# BGC_main.net
KiCad netlist of a schematic drawn in EAGLE
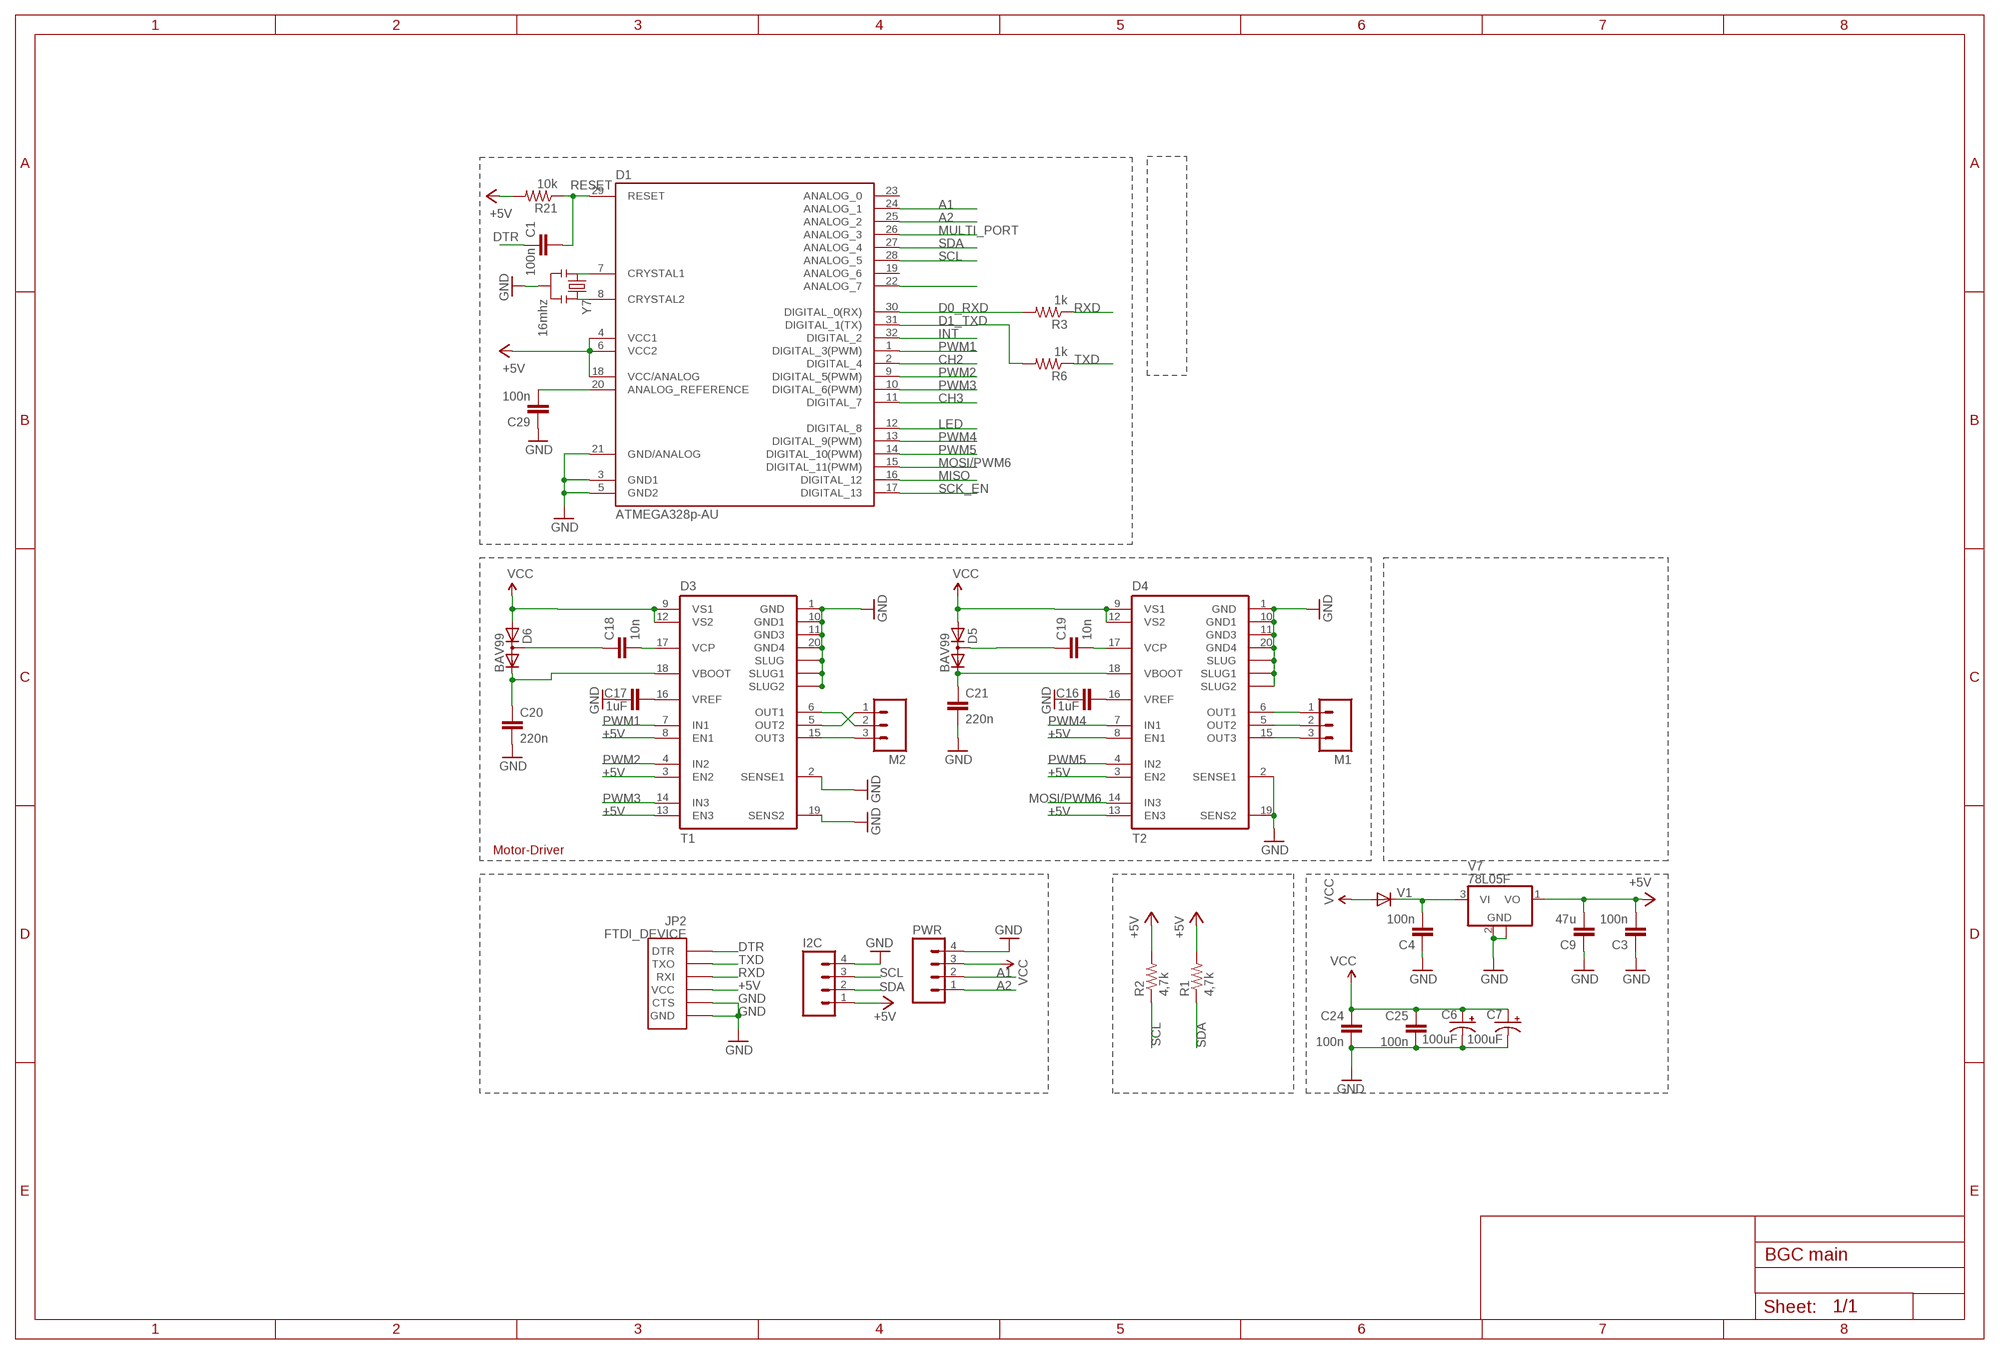
[diagram p0: schematic, sheet 1]

(export (version "E")
  (design (tool "Eeschema 10.0.6"))
  (components
    (comp (ref "C1")
      (value "100n")
      (footprint "eagle-import:0402-CAP")
      (libsource (lib "eagle-import") (part "CAP0402-CAP"))
    )
    (comp (ref "C3")
      (value "100n")
      (footprint "eagle-import:0402-CAP")
      (libsource (lib "eagle-import") (part "CAP0402-CAP"))
    )
    (comp (ref "C4")
      (value "100n")
      (footprint "eagle-import:0402-CAP")
      (libsource (lib "eagle-import") (part "CAP0402-CAP"))
    )
    (comp (ref "C6")
      (value "100uF")
      (footprint "eagle-import:EIA7343")
      (libsource (lib "eagle-import") (part "100UF-10V-10%(TANT)"))
    )
    (comp (ref "C7")
      (value "100uF")
      (footprint "eagle-import:EIA7343")
      (libsource (lib "eagle-import") (part "100UF-10V-10%(TANT)"))
    )
    (comp (ref "C9")
      (value "47u")
      (footprint "eagle-import:C1210")
      (libsource (lib "eagle-import") (part "C-EUC1210"))
    )
    (comp (ref "C16")
      (value "1uF")
      (footprint "eagle-import:0402-CAP")
      (libsource (lib "eagle-import") (part "CAP0402-CAP"))
    )
    (comp (ref "C17")
      (value "1uF")
      (footprint "eagle-import:0402-CAP")
      (libsource (lib "eagle-import") (part "CAP0402-CAP"))
    )
    (comp (ref "C18")
      (value "10n")
      (footprint "eagle-import:0402-CAP")
      (libsource (lib "eagle-import") (part "CAP0402-CAP"))
    )
    (comp (ref "C19")
      (value "10n")
      (footprint "eagle-import:0402-CAP")
      (libsource (lib "eagle-import") (part "CAP0402-CAP"))
    )
    (comp (ref "C20")
      (value "220n")
      (footprint "eagle-import:0402-CAP")
      (libsource (lib "eagle-import") (part "CAP0402-CAP"))
    )
    (comp (ref "C21")
      (value "220n")
      (footprint "eagle-import:0402-CAP")
      (libsource (lib "eagle-import") (part "CAP0402-CAP"))
    )
    (comp (ref "C24")
      (value "100n")
      (footprint "eagle-import:0402-CAP")
      (libsource (lib "eagle-import") (part "CAP0402-CAP"))
    )
    (comp (ref "C25")
      (value "100n")
      (footprint "eagle-import:0402-CAP")
      (libsource (lib "eagle-import") (part "CAP0402-CAP"))
    )
    (comp (ref "C29")
      (value "100n")
      (footprint "eagle-import:0402-CAP")
      (libsource (lib "eagle-import") (part "CAP0402-CAP"))
    )
    (comp (ref "D1")
      (value "ATMEGA328p-AU")
      (footprint "eagle-import:TQFP32-08")
      (libsource (lib "eagle-import") (part "ATMEGA168-AU"))
    )
    (comp (ref "D3")
      (value "T1")
      (footprint "eagle-import:SO20POWER2")
      (libsource (lib "eagle-import") (part "L6234"))
    )
    (comp (ref "D4")
      (value "T2")
      (footprint "eagle-import:SO20POWER2")
      (libsource (lib "eagle-import") (part "L6234"))
    )
    (comp (ref "D5")
      (value "BAV99")
      (footprint "eagle-import:SOT23")
      (libsource (lib "eagle-import") (part "BAV199"))
    )
    (comp (ref "D6")
      (value "BAV99")
      (footprint "eagle-import:SOT23")
      (libsource (lib "eagle-import") (part "BAV199"))
    )
    (comp (ref "I2C")
      (value "M04PTH")
      (footprint "eagle-import:1X04")
      (libsource (lib "eagle-import") (part "M04PTH"))
    )
    (comp (ref "JP2")
      (value "FTDI_DEVICE")
      (footprint "eagle-import:FTDI_DEVICE_SIDE")
      (libsource (lib "eagle-import") (part "FTDI_DEVICE"))
    )
    (comp (ref "M1")
      (value "M03PTH")
      (footprint "eagle-import:1X03")
      (libsource (lib "eagle-import") (part "M03PTH"))
    )
    (comp (ref "M2")
      (value "M03PTH")
      (footprint "eagle-import:1X03")
      (libsource (lib "eagle-import") (part "M03PTH"))
    )
    (comp (ref "PWR")
      (value "M04PTH")
      (footprint "eagle-import:1X04")
      (libsource (lib "eagle-import") (part "M04PTH"))
    )
    (comp (ref "R1")
      (value "4,7k")
      (footprint "eagle-import:0402-RES")
      (libsource (lib "eagle-import") (part "RESISTOR0402-RES"))
    )
    (comp (ref "R2")
      (value "4,7k")
      (footprint "eagle-import:0402-RES")
      (libsource (lib "eagle-import") (part "RESISTOR0402-RES"))
    )
    (comp (ref "R3")
      (value "1k")
      (footprint "eagle-import:0402-RES")
      (libsource (lib "eagle-import") (part "RESISTOR0402-RES"))
    )
    (comp (ref "R6")
      (value "1k")
      (footprint "eagle-import:0402-RES")
      (libsource (lib "eagle-import") (part "RESISTOR0402-RES"))
    )
    (comp (ref "R21")
      (value "10k")
      (footprint "eagle-import:0402-RES")
      (libsource (lib "eagle-import") (part "RESISTOR0402-RES"))
    )
    (comp (ref "V1")
      (value "DIODE-DO214AC")
      (footprint "eagle-import:DO214AC")
      (libsource (lib "eagle-import") (part "DIODE-DO214AC"))
    )
    (comp (ref "V7")
      (value "78L05F")
      (footprint "eagle-import:SOT89")
      (libsource (lib "eagle-import") (part "78LF05"))
    )
    (comp (ref "Y7")
      (value "16mhz")
      (footprint "eagle-import:RESONATOR-SMD")
      (libsource (lib "eagle-import") (part "RESONATORSMD"))
    )
  )
  (nets
    (net (code "1") (name "+5V") (class "Default")
      (node (ref "C3") (pin "2") (pinfunction "2_2") (pintype "passive"))
      (node (ref "C9") (pin "2") (pinfunction "2_2") (pintype "passive"))
      (node (ref "D1") (pin "18") (pinfunction "VCC/ANALOG_18") (pintype "passive"))
      (node (ref "D1") (pin "4") (pinfunction "VCC1_4") (pintype "power_in"))
      (node (ref "D1") (pin "6") (pinfunction "VCC2_6") (pintype "power_in"))
      (node (ref "D3") (pin "13") (pinfunction "EN3_13") (pintype "output"))
      (node (ref "D3") (pin "3") (pinfunction "EN2_3") (pintype "input"))
      (node (ref "D3") (pin "8") (pinfunction "EN1_8") (pintype "bidirectional"))
      (node (ref "D4") (pin "13") (pinfunction "EN3_13") (pintype "output"))
      (node (ref "D4") (pin "3") (pinfunction "EN2_3") (pintype "input"))
      (node (ref "D4") (pin "8") (pinfunction "EN1_8") (pintype "bidirectional"))
      (node (ref "I2C") (pin "1") (pinfunction "1_1") (pintype "passive"))
      (node (ref "JP2") (pin "P$4") (pinfunction "VCC_P$4") (pintype "bidirectional"))
      (node (ref "R1") (pin "2") (pinfunction "2_2") (pintype "passive"))
      (node (ref "R2") (pin "2") (pinfunction "2_2") (pintype "passive"))
      (node (ref "R21") (pin "2") (pinfunction "2_2") (pintype "passive"))
      (node (ref "V7") (pin "1") (pinfunction "VO_1") (pintype "passive"))
    )
    (net (code "2") (name "/A1") (class "Default")
      (node (ref "D1") (pin "24") (pinfunction "ANALOG_1_24") (pintype "bidirectional"))
      (node (ref "PWR") (pin "2") (pinfunction "2_2") (pintype "passive"))
    )
    (net (code "3") (name "/A2") (class "Default")
      (node (ref "D1") (pin "25") (pinfunction "ANALOG_2_25") (pintype "bidirectional"))
      (node (ref "PWR") (pin "1") (pinfunction "1_1") (pintype "passive"))
    )
    (net (code "4") (name "/CH2") (class "Default")
      (node (ref "D1") (pin "2") (pinfunction "DIGITAL_4_2") (pintype "bidirectional"))
    )
    (net (code "5") (name "/CH3") (class "Default")
      (node (ref "D1") (pin "11") (pinfunction "DIGITAL_7_11") (pintype "bidirectional"))
    )
    (net (code "6") (name "/D0_RXD") (class "Default")
      (node (ref "D1") (pin "30") (pinfunction "DIGITAL_0(RX)_30") (pintype "bidirectional"))
      (node (ref "R3") (pin "2") (pinfunction "2_2") (pintype "passive"))
    )
    (net (code "7") (name "/D1_TXD") (class "Default")
      (node (ref "D1") (pin "31") (pinfunction "DIGITAL_1(TX)_31") (pintype "bidirectional"))
      (node (ref "R6") (pin "2") (pinfunction "2_2") (pintype "passive"))
    )
    (net (code "8") (name "/DTR") (class "Default")
      (node (ref "C1") (pin "1") (pinfunction "1_1") (pintype "passive"))
      (node (ref "JP2") (pin "P$1") (pinfunction "DTR_P$1") (pintype "bidirectional"))
    )
    (net (code "9") (name "/INT") (class "Default")
      (node (ref "D1") (pin "32") (pinfunction "DIGITAL_2_32") (pintype "bidirectional"))
    )
    (net (code "10") (name "/LED") (class "Default")
      (node (ref "D1") (pin "12") (pinfunction "DIGITAL_8_12") (pintype "bidirectional"))
    )
    (net (code "11") (name "/MISO") (class "Default")
      (node (ref "D1") (pin "16") (pinfunction "DIGITAL_12_16") (pintype "bidirectional"))
    )
    (net (code "12") (name "/MOSI{slash}PWM6") (class "Default")
      (node (ref "D1") (pin "15") (pinfunction "DIGITAL_11(PWM)_15") (pintype "bidirectional"))
      (node (ref "D4") (pin "14") (pinfunction "IN3_14") (pintype "bidirectional"))
    )
    (net (code "13") (name "/MULTI_PORT") (class "Default")
      (node (ref "D1") (pin "26") (pinfunction "ANALOG_3_26") (pintype "bidirectional"))
    )
    (net (code "14") (name "/PWM1") (class "Default")
      (node (ref "D1") (pin "1") (pinfunction "DIGITAL_3(PWM)_1") (pintype "bidirectional"))
      (node (ref "D3") (pin "7") (pinfunction "IN1_7") (pintype "input"))
    )
    (net (code "15") (name "/PWM2") (class "Default")
      (node (ref "D1") (pin "9") (pinfunction "DIGITAL_5(PWM)_9") (pintype "bidirectional"))
      (node (ref "D3") (pin "4") (pinfunction "IN2_4") (pintype "input"))
    )
    (net (code "16") (name "/PWM3") (class "Default")
      (node (ref "D1") (pin "10") (pinfunction "DIGITAL_6(PWM)_10") (pintype "bidirectional"))
      (node (ref "D3") (pin "14") (pinfunction "IN3_14") (pintype "bidirectional"))
    )
    (net (code "17") (name "/PWM4") (class "Default")
      (node (ref "D1") (pin "13") (pinfunction "DIGITAL_9(PWM)_13") (pintype "bidirectional"))
      (node (ref "D4") (pin "7") (pinfunction "IN1_7") (pintype "input"))
    )
    (net (code "18") (name "/PWM5") (class "Default")
      (node (ref "D1") (pin "14") (pinfunction "DIGITAL_10(PWM)_14") (pintype "bidirectional"))
      (node (ref "D4") (pin "4") (pinfunction "IN2_4") (pintype "input"))
    )
    (net (code "19") (name "/RESET") (class "Default")
      (node (ref "C1") (pin "2") (pinfunction "2_2") (pintype "passive"))
      (node (ref "D1") (pin "29") (pinfunction "RESET_29") (pintype "bidirectional"))
      (node (ref "R21") (pin "1") (pinfunction "1_1") (pintype "passive"))
    )
    (net (code "20") (name "/RXD") (class "Default")
      (node (ref "JP2") (pin "P$3") (pinfunction "RXI_P$3") (pintype "bidirectional"))
      (node (ref "R3") (pin "1") (pinfunction "1_1") (pintype "passive"))
    )
    (net (code "21") (name "/SCK_EN") (class "Default")
      (node (ref "D1") (pin "17") (pinfunction "DIGITAL_13_17") (pintype "bidirectional"))
    )
    (net (code "22") (name "/SCL") (class "Default")
      (node (ref "D1") (pin "28") (pinfunction "ANALOG_5_28") (pintype "bidirectional"))
      (node (ref "I2C") (pin "3") (pinfunction "3_3") (pintype "passive"))
      (node (ref "R2") (pin "1") (pinfunction "1_1") (pintype "passive"))
    )
    (net (code "23") (name "/SDA") (class "Default")
      (node (ref "D1") (pin "27") (pinfunction "ANALOG_4_27") (pintype "bidirectional"))
      (node (ref "I2C") (pin "2") (pinfunction "2_2") (pintype "passive"))
      (node (ref "R1") (pin "1") (pinfunction "1_1") (pintype "passive"))
    )
    (net (code "24") (name "/TXD") (class "Default")
      (node (ref "JP2") (pin "P$2") (pinfunction "TXO_P$2") (pintype "bidirectional"))
      (node (ref "R6") (pin "1") (pinfunction "1_1") (pintype "passive"))
    )
    (net (code "25") (name "GND") (class "Default")
      (node (ref "C16") (pin "1") (pinfunction "1_1") (pintype "passive"))
      (node (ref "C17") (pin "1") (pinfunction "1_1") (pintype "passive"))
      (node (ref "C20") (pin "2") (pinfunction "2_2") (pintype "passive"))
      (node (ref "C21") (pin "2") (pinfunction "2_2") (pintype "passive"))
      (node (ref "C24") (pin "2") (pinfunction "2_2") (pintype "passive"))
      (node (ref "C25") (pin "2") (pinfunction "2_2") (pintype "passive"))
      (node (ref "C29") (pin "1") (pinfunction "1_1") (pintype "passive"))
      (node (ref "C3") (pin "1") (pinfunction "1_1") (pintype "passive"))
      (node (ref "C4") (pin "1") (pinfunction "1_1") (pintype "passive"))
      (node (ref "C6") (pin "C") (pinfunction "-_C") (pintype "passive"))
      (node (ref "C7") (pin "C") (pinfunction "-_C") (pintype "passive"))
      (node (ref "C9") (pin "1") (pinfunction "1_1") (pintype "passive"))
      (node (ref "D1") (pin "21") (pinfunction "GND/ANALOG_21") (pintype "power_in"))
      (node (ref "D1") (pin "3") (pinfunction "GND1_3") (pintype "power_in"))
      (node (ref "D1") (pin "5") (pinfunction "GND2_5") (pintype "power_in"))
      (node (ref "D3") (pin "1") (pinfunction "GND_1") (pintype "power_in"))
      (node (ref "D3") (pin "10") (pinfunction "GND1_10") (pintype "power_in"))
      (node (ref "D3") (pin "11") (pinfunction "GND3_11") (pintype "power_in"))
      (node (ref "D3") (pin "19") (pinfunction "SENS2_19") (pintype "power_in"))
      (node (ref "D3") (pin "2") (pinfunction "SENSE1_2") (pintype "output"))
      (node (ref "D3") (pin "20") (pinfunction "GND4_20") (pintype "power_in"))
      (node (ref "D3") (pin "SLUG") (pinfunction "SLUG1_SLUG") (pintype "power_in"))
      (node (ref "D3") (pin "SLUG1") (pinfunction "SLUG2_SLUG1") (pintype "power_in"))
      (node (ref "D3") (pin "SLUG2") (pinfunction "SLUG_SLUG2") (pintype "power_in"))
      (node (ref "D4") (pin "1") (pinfunction "GND_1") (pintype "power_in"))
      (node (ref "D4") (pin "10") (pinfunction "GND1_10") (pintype "power_in"))
      (node (ref "D4") (pin "11") (pinfunction "GND3_11") (pintype "power_in"))
      (node (ref "D4") (pin "19") (pinfunction "SENS2_19") (pintype "power_in"))
      (node (ref "D4") (pin "2") (pinfunction "SENSE1_2") (pintype "output"))
      (node (ref "D4") (pin "20") (pinfunction "GND4_20") (pintype "power_in"))
      (node (ref "D4") (pin "SLUG") (pinfunction "SLUG1_SLUG") (pintype "power_in"))
      (node (ref "D4") (pin "SLUG1") (pinfunction "SLUG2_SLUG1") (pintype "power_in"))
      (node (ref "D4") (pin "SLUG2") (pinfunction "SLUG_SLUG2") (pintype "power_in"))
      (node (ref "I2C") (pin "4") (pinfunction "4_4") (pintype "passive"))
      (node (ref "JP2") (pin "P$5") (pinfunction "CTS_P$5") (pintype "bidirectional"))
      (node (ref "JP2") (pin "P$6") (pinfunction "GND_P$6") (pintype "bidirectional"))
      (node (ref "PWR") (pin "4") (pinfunction "4_4") (pintype "passive"))
      (node (ref "V7") (pin "2") (pinfunction "GND_2") (pintype "passive"))
      (node (ref "V7") (pin "2@1") (pinfunction "GND_2@1") (pintype "passive"))
      (node (ref "Y7") (pin "2") (pinfunction "2_2") (pintype "passive"))
    )
    (net (code "26") (name "Net-(D1-ANALOG_REFERENCE)") (class "Default")
      (node (ref "C29") (pin "2") (pinfunction "2_2") (pintype "passive"))
      (node (ref "D1") (pin "20") (pinfunction "ANALOG_REFERENCE_20") (pintype "passive"))
    )
    (net (code "27") (name "Net-(D1-CRYSTAL1)") (class "Default")
      (node (ref "D1") (pin "7") (pinfunction "CRYSTAL1_7") (pintype "bidirectional"))
      (node (ref "Y7") (pin "1") (pinfunction "1_1") (pintype "passive"))
    )
    (net (code "28") (name "Net-(D1-CRYSTAL2)") (class "Default")
      (node (ref "D1") (pin "8") (pinfunction "CRYSTAL2_8") (pintype "bidirectional"))
      (node (ref "Y7") (pin "3") (pinfunction "3_3") (pintype "passive"))
    )
    (net (code "29") (name "Net-(D3-OUT1)") (class "Default")
      (node (ref "D3") (pin "6") (pinfunction "OUT1_6") (pintype "output"))
      (node (ref "M2") (pin "2") (pinfunction "2_2") (pintype "passive"))
    )
    (net (code "30") (name "Net-(D3-OUT2)") (class "Default")
      (node (ref "D3") (pin "5") (pinfunction "OUT2_5") (pintype "output"))
      (node (ref "M2") (pin "1") (pinfunction "1_1") (pintype "passive"))
    )
    (net (code "31") (name "Net-(D3-OUT3)") (class "Default")
      (node (ref "D3") (pin "15") (pinfunction "OUT3_15") (pintype "power_in"))
      (node (ref "M2") (pin "3") (pinfunction "3_3") (pintype "passive"))
    )
    (net (code "32") (name "Net-(D3-VBOOT)") (class "Default")
      (node (ref "C20") (pin "1") (pinfunction "1_1") (pintype "passive"))
      (node (ref "D3") (pin "18") (pinfunction "VBOOT_18") (pintype "passive"))
      (node (ref "D6") (pin "2") (pinfunction "C_2") (pintype "passive"))
    )
    (net (code "33") (name "Net-(D3-VCP)") (class "Default")
      (node (ref "C18") (pin "2") (pinfunction "2_2") (pintype "passive"))
      (node (ref "D3") (pin "17") (pinfunction "VCP_17") (pintype "passive"))
    )
    (net (code "34") (name "Net-(D3-VREF)") (class "Default")
      (node (ref "C17") (pin "2") (pinfunction "2_2") (pintype "passive"))
      (node (ref "D3") (pin "16") (pinfunction "VREF_16") (pintype "input"))
    )
    (net (code "35") (name "Net-(D4-OUT1)") (class "Default")
      (node (ref "D4") (pin "6") (pinfunction "OUT1_6") (pintype "output"))
      (node (ref "M1") (pin "1") (pinfunction "1_1") (pintype "passive"))
    )
    (net (code "36") (name "Net-(D4-OUT2)") (class "Default")
      (node (ref "D4") (pin "5") (pinfunction "OUT2_5") (pintype "output"))
      (node (ref "M1") (pin "2") (pinfunction "2_2") (pintype "passive"))
    )
    (net (code "37") (name "Net-(D4-OUT3)") (class "Default")
      (node (ref "D4") (pin "15") (pinfunction "OUT3_15") (pintype "power_in"))
      (node (ref "M1") (pin "3") (pinfunction "3_3") (pintype "passive"))
    )
    (net (code "38") (name "Net-(D4-VBOOT)") (class "Default")
      (node (ref "C21") (pin "1") (pinfunction "1_1") (pintype "passive"))
      (node (ref "D4") (pin "18") (pinfunction "VBOOT_18") (pintype "passive"))
      (node (ref "D5") (pin "2") (pinfunction "C_2") (pintype "passive"))
    )
    (net (code "39") (name "Net-(D4-VCP)") (class "Default")
      (node (ref "C19") (pin "2") (pinfunction "2_2") (pintype "passive"))
      (node (ref "D4") (pin "17") (pinfunction "VCP_17") (pintype "passive"))
    )
    (net (code "40") (name "Net-(D4-VREF)") (class "Default")
      (node (ref "C16") (pin "2") (pinfunction "2_2") (pintype "passive"))
      (node (ref "D4") (pin "16") (pinfunction "VREF_16") (pintype "input"))
    )
    (net (code "41") (name "Net-(D5-AC)") (class "Default")
      (node (ref "C19") (pin "1") (pinfunction "1_1") (pintype "passive"))
      (node (ref "D5") (pin "3") (pinfunction "AC_3") (pintype "passive"))
    )
    (net (code "42") (name "Net-(D6-AC)") (class "Default")
      (node (ref "C18") (pin "1") (pinfunction "1_1") (pintype "passive"))
      (node (ref "D6") (pin "3") (pinfunction "AC_3") (pintype "passive"))
    )
    (net (code "43") (name "Net-(V7-VI)") (class "Default")
      (node (ref "C4") (pin "2") (pinfunction "2_2") (pintype "passive"))
      (node (ref "V1") (pin "C") (pinfunction "C_C") (pintype "passive"))
      (node (ref "V7") (pin "3") (pinfunction "VI_3") (pintype "input"))
    )
    (net (code "44") (name "VCC") (class "Default")
      (node (ref "C24") (pin "1") (pinfunction "1_1") (pintype "passive"))
      (node (ref "C25") (pin "1") (pinfunction "1_1") (pintype "passive"))
      (node (ref "C6") (pin "A") (pinfunction "+_A") (pintype "passive"))
      (node (ref "C7") (pin "A") (pinfunction "+_A") (pintype "passive"))
      (node (ref "D3") (pin "12") (pinfunction "VS2_12") (pintype "power_in"))
      (node (ref "D3") (pin "9") (pinfunction "VS1_9") (pintype "power_in"))
      (node (ref "D4") (pin "12") (pinfunction "VS2_12") (pintype "power_in"))
      (node (ref "D4") (pin "9") (pinfunction "VS1_9") (pintype "power_in"))
      (node (ref "D5") (pin "1") (pinfunction "A_1") (pintype "passive"))
      (node (ref "D6") (pin "1") (pinfunction "A_1") (pintype "passive"))
      (node (ref "PWR") (pin "3") (pinfunction "3_3") (pintype "passive"))
      (node (ref "V1") (pin "A") (pinfunction "A_A") (pintype "passive"))
    )
    (net (code "45") (name "unconnected-(D1-ANALOG_0-Pad23)") (class "Default")
      (node (ref "D1") (pin "23") (pinfunction "ANALOG_0_23") (pintype "bidirectional"))
    )
    (net (code "46") (name "unconnected-(D1-ANALOG_6-Pad19)") (class "Default")
      (node (ref "D1") (pin "19") (pinfunction "ANALOG_6_19") (pintype "passive"))
    )
    (net (code "47") (name "unconnected-(D1-ANALOG_7-Pad22)") (class "Default")
      (node (ref "D1") (pin "22") (pinfunction "ANALOG_7_22") (pintype "passive"))
    )
  )
)
